# Audio.net
KiCad netlist of a schematic drawn in Altium Designer
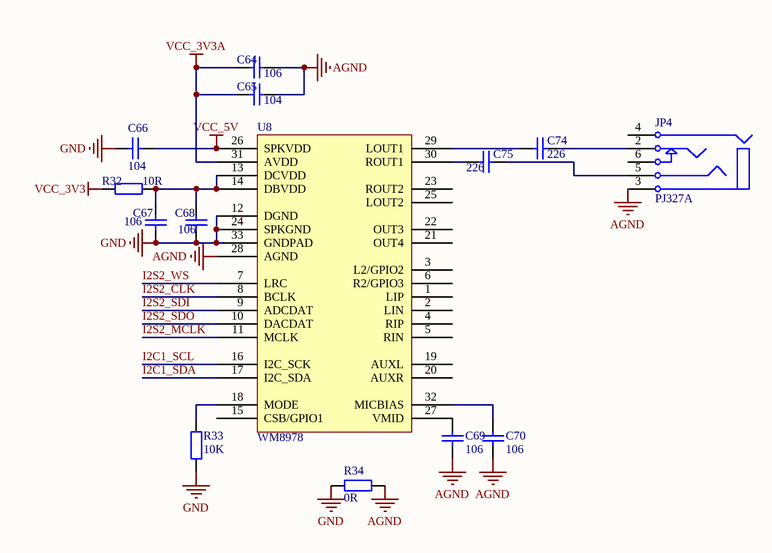
[diagram p0: Audio.SchDoc]

(export (version "E")
  (design (tool "Eeschema 10.0.6"))
  (components
    (comp (ref "C64")
      (value "106")
      (footprint "C0402_M")
      (description "贴片电容/MLCC电容")
      (libsource (lib "0.1 - 电阻-电容-电感-晶振-晶体-磁珠-电位器-法拉电容-馈通电容") (part "C"))
    )
    (comp (ref "C65")
      (value "104")
      (footprint "C0402_M")
      (description "贴片电容/MLCC电容")
      (libsource (lib "0.1 - 电阻-电容-电感-晶振-晶体-磁珠-电位器-法拉电容-馈通电容") (part "C"))
    )
    (comp (ref "C66")
      (value "104")
      (footprint "C0402_M")
      (description "贴片电容/MLCC电容")
      (libsource (lib "0.1 - 电阻-电容-电感-晶振-晶体-磁珠-电位器-法拉电容-馈通电容") (part "C"))
    )
    (comp (ref "C67")
      (value "106")
      (footprint "C0402_M")
      (description "贴片电容/MLCC电容")
      (libsource (lib "0.1 - 电阻-电容-电感-晶振-晶体-磁珠-电位器-法拉电容-馈通电容") (part "C"))
    )
    (comp (ref "C68")
      (value "106")
      (footprint "C0402_M")
      (description "贴片电容/MLCC电容")
      (libsource (lib "0.1 - 电阻-电容-电感-晶振-晶体-磁珠-电位器-法拉电容-馈通电容") (part "C"))
    )
    (comp (ref "C69")
      (value "106")
      (footprint "C0402_M")
      (description "贴片电容/MLCC电容")
      (libsource (lib "0.1 - 电阻-电容-电感-晶振-晶体-磁珠-电位器-法拉电容-馈通电容") (part "C"))
    )
    (comp (ref "C70")
      (value "106")
      (footprint "C0402_M")
      (description "贴片电容/MLCC电容")
      (libsource (lib "0.1 - 电阻-电容-电感-晶振-晶体-磁珠-电位器-法拉电容-馈通电容") (part "C"))
    )
    (comp (ref "C74")
      (value "226")
      (footprint "C0805_M")
      (description "贴片电容/MLCC电容")
      (libsource (lib "0.1 - 电阻-电容-电感-晶振-晶体-磁珠-电位器-法拉电容-馈通电容") (part "C"))
    )
    (comp (ref "C75")
      (value "226")
      (footprint "C0805_M")
      (description "贴片电容/MLCC电容")
      (libsource (lib "0.1 - 电阻-电容-电感-晶振-晶体-磁珠-电位器-法拉电容-馈通电容") (part "C"))
    )
    (comp (ref "JP4")
      (value "PJ327A")
      (footprint "PJ327A")
      (description "3.5mm音频接口")
      (libsource (lib "MySchlib") (part "PJ327A"))
    )
    (comp (ref "R32")
      (value "10R")
      (footprint "R0603_M")
      (description "贴片电阻")
      (libsource (lib "0.1 - 电阻-电容-电感-晶振-晶体-磁珠-电位器-法拉电容-馈通电容") (part "R"))
    )
    (comp (ref "R33")
      (value "10K")
      (footprint "R0402_M")
      (description "贴片电阻")
      (libsource (lib "0.1 - 电阻-电容-电感-晶振-晶体-磁珠-电位器-法拉电容-馈通电容") (part "R"))
    )
    (comp (ref "R34")
      (value "0R")
      (footprint "R0603_M")
      (description "贴片电阻")
      (libsource (lib "0.1 - 电阻-电容-电感-晶振-晶体-磁珠-电位器-法拉电容-馈通电容") (part "R"))
    )
    (comp (ref "U8") (value "WM8978") (footprint "QFN32 5x5_N") (libsource (lib "MySchlib") (part "WM8978")))
  )
  (nets
    (net (code "1") (name "/I2C1_SCL") (class "Default")
      (node (ref "U8") (pin "16") (pinfunction "I2C_SCK_16") (pintype "passive"))
    )
    (net (code "2") (name "/I2C1_SDA") (class "Default")
      (node (ref "U8") (pin "17") (pinfunction "I2C_SDA_17") (pintype "passive"))
    )
    (net (code "3") (name "/I2S2_CLK") (class "Default")
      (node (ref "U8") (pin "8") (pinfunction "BCLK_8") (pintype "passive"))
    )
    (net (code "4") (name "/I2S2_MCLK") (class "Default")
      (node (ref "U8") (pin "11") (pinfunction "MCLK_11") (pintype "passive"))
    )
    (net (code "5") (name "/I2S2_SDI") (class "Default")
      (node (ref "U8") (pin "9") (pinfunction "ADCDAT_9") (pintype "passive"))
    )
    (net (code "6") (name "/I2S2_SDO") (class "Default")
      (node (ref "U8") (pin "10") (pinfunction "DACDAT_10") (pintype "passive"))
    )
    (net (code "7") (name "/I2S2_WS") (class "Default")
      (node (ref "U8") (pin "7") (pinfunction "LRC_7") (pintype "passive"))
    )
    (net (code "8") (name "AGND") (class "Default")
      (node (ref "C64") (pin "1") (pinfunction "1_1") (pintype "passive"))
      (node (ref "C65") (pin "1") (pinfunction "1_1") (pintype "passive"))
      (node (ref "C69") (pin "1") (pinfunction "1_1") (pintype "passive"))
      (node (ref "C70") (pin "1") (pinfunction "1_1") (pintype "passive"))
      (node (ref "JP4") (pin "3") (pinfunction "3_3") (pintype "passive"))
      (node (ref "R34") (pin "1") (pinfunction "1_1") (pintype "passive"))
      (node (ref "U8") (pin "28") (pinfunction "AGND_28") (pintype "passive"))
    )
    (net (code "9") (name "GND") (class "Default")
      (node (ref "C66") (pin "1") (pinfunction "1_1") (pintype "passive"))
      (node (ref "C67") (pin "2") (pinfunction "2_2") (pintype "passive"))
      (node (ref "C68") (pin "2") (pinfunction "2_2") (pintype "passive"))
      (node (ref "R33") (pin "1") (pinfunction "1_1") (pintype "passive"))
      (node (ref "R34") (pin "2") (pinfunction "2_2") (pintype "passive"))
      (node (ref "U8") (pin "12") (pinfunction "DGND_12") (pintype "passive"))
      (node (ref "U8") (pin "24") (pinfunction "SPKGND_24") (pintype "passive"))
      (node (ref "U8") (pin "33") (pinfunction "GNDPAD_33") (pintype "passive"))
    )
    (net (code "10") (name "Net-(C74-Pad2)") (class "Default")
      (node (ref "C74") (pin "2") (pinfunction "2_2") (pintype "passive"))
      (node (ref "JP4") (pin "2") (pinfunction "2_2") (pintype "passive"))
    )
    (net (code "11") (name "Net-(C75-Pad2)") (class "Default")
      (node (ref "C75") (pin "2") (pinfunction "2_2") (pintype "passive"))
      (node (ref "JP4") (pin "5") (pinfunction "5_5") (pintype "passive"))
    )
    (net (code "12") (name "Net-(U8-DBVDD)") (class "Default")
      (node (ref "C67") (pin "1") (pinfunction "1_1") (pintype "passive"))
      (node (ref "C68") (pin "1") (pinfunction "1_1") (pintype "passive"))
      (node (ref "R32") (pin "1") (pinfunction "1_1") (pintype "passive"))
      (node (ref "U8") (pin "13") (pinfunction "DCVDD_13") (pintype "passive"))
      (node (ref "U8") (pin "14") (pinfunction "DBVDD_14") (pintype "passive"))
    )
    (net (code "13") (name "Net-(U8-LOUT1)") (class "Default")
      (node (ref "C74") (pin "1") (pinfunction "1_1") (pintype "passive"))
      (node (ref "U8") (pin "29") (pinfunction "LOUT1_29") (pintype "passive"))
    )
    (net (code "14") (name "Net-(U8-MICBIAS)") (class "Default")
      (node (ref "C70") (pin "2") (pinfunction "2_2") (pintype "passive"))
      (node (ref "U8") (pin "32") (pinfunction "MICBIAS_32") (pintype "passive"))
    )
    (net (code "15") (name "Net-(U8-MODE)") (class "Default")
      (node (ref "R33") (pin "2") (pinfunction "2_2") (pintype "passive"))
      (node (ref "U8") (pin "18") (pinfunction "MODE_18") (pintype "passive"))
    )
    (net (code "16") (name "Net-(U8-ROUT1)") (class "Default")
      (node (ref "C75") (pin "1") (pinfunction "1_1") (pintype "passive"))
      (node (ref "U8") (pin "30") (pinfunction "ROUT1_30") (pintype "passive"))
    )
    (net (code "17") (name "Net-(U8-VMID)") (class "Default")
      (node (ref "C69") (pin "2") (pinfunction "2_2") (pintype "passive"))
      (node (ref "U8") (pin "27") (pinfunction "VMID_27") (pintype "passive"))
    )
    (net (code "18") (name "VCC_3V3") (class "Default")
      (node (ref "R32") (pin "2") (pinfunction "2_2") (pintype "passive"))
    )
    (net (code "19") (name "VCC_3V3A") (class "Default")
      (node (ref "C64") (pin "2") (pinfunction "2_2") (pintype "passive"))
      (node (ref "C65") (pin "2") (pinfunction "2_2") (pintype "passive"))
      (node (ref "U8") (pin "31") (pinfunction "AVDD_31") (pintype "passive"))
    )
    (net (code "20") (name "VCC_5V") (class "Default")
      (node (ref "C66") (pin "2") (pinfunction "2_2") (pintype "passive"))
      (node (ref "U8") (pin "26") (pinfunction "SPKVDD_26") (pintype "passive"))
    )
    (net (code "21") (name "unconnected-(JP4-Pad4)") (class "Default")
      (node (ref "JP4") (pin "4") (pinfunction "4_4") (pintype "passive"))
    )
    (net (code "22") (name "unconnected-(JP4-Pad6)") (class "Default")
      (node (ref "JP4") (pin "6") (pinfunction "6_6") (pintype "passive"))
    )
    (net (code "23") (name "unconnected-(U8-AUXL-Pad19)") (class "Default")
      (node (ref "U8") (pin "19") (pinfunction "AUXL_19") (pintype "passive"))
    )
    (net (code "24") (name "unconnected-(U8-AUXR-Pad20)") (class "Default")
      (node (ref "U8") (pin "20") (pinfunction "AUXR_20") (pintype "passive"))
    )
    (net (code "25") (name "unconnected-(U8-CSB{slash}GPIO1-Pad15)") (class "Default")
      (node (ref "U8") (pin "15") (pinfunction "CSB/GPIO1_15") (pintype "passive"))
    )
    (net (code "26") (name "unconnected-(U8-L2{slash}GPIO2-Pad3)") (class "Default")
      (node (ref "U8") (pin "3") (pinfunction "L2/GPIO2_3") (pintype "passive"))
    )
    (net (code "27") (name "unconnected-(U8-LIN-Pad2)") (class "Default")
      (node (ref "U8") (pin "2") (pinfunction "LIN_2") (pintype "passive"))
    )
    (net (code "28") (name "unconnected-(U8-LIP-Pad1)") (class "Default")
      (node (ref "U8") (pin "1") (pinfunction "LIP_1") (pintype "passive"))
    )
    (net (code "29") (name "unconnected-(U8-LOUT2-Pad25)") (class "Default")
      (node (ref "U8") (pin "25") (pinfunction "LOUT2_25") (pintype "passive"))
    )
    (net (code "30") (name "unconnected-(U8-OUT3-Pad22)") (class "Default")
      (node (ref "U8") (pin "22") (pinfunction "OUT3_22") (pintype "passive"))
    )
    (net (code "31") (name "unconnected-(U8-OUT4-Pad21)") (class "Default")
      (node (ref "U8") (pin "21") (pinfunction "OUT4_21") (pintype "passive"))
    )
    (net (code "32") (name "unconnected-(U8-R2{slash}GPIO3-Pad6)") (class "Default")
      (node (ref "U8") (pin "6") (pinfunction "R2/GPIO3_6") (pintype "passive"))
    )
    (net (code "33") (name "unconnected-(U8-RIN-Pad5)") (class "Default")
      (node (ref "U8") (pin "5") (pinfunction "RIN_5") (pintype "passive"))
    )
    (net (code "34") (name "unconnected-(U8-RIP-Pad4)") (class "Default")
      (node (ref "U8") (pin "4") (pinfunction "RIP_4") (pintype "passive"))
    )
    (net (code "35") (name "unconnected-(U8-ROUT2-Pad23)") (class "Default")
      (node (ref "U8") (pin "23") (pinfunction "ROUT2_23") (pintype "passive"))
    )
  )
)
